# PISO3.net
KiCad netlist of a schematic drawn in EAGLE
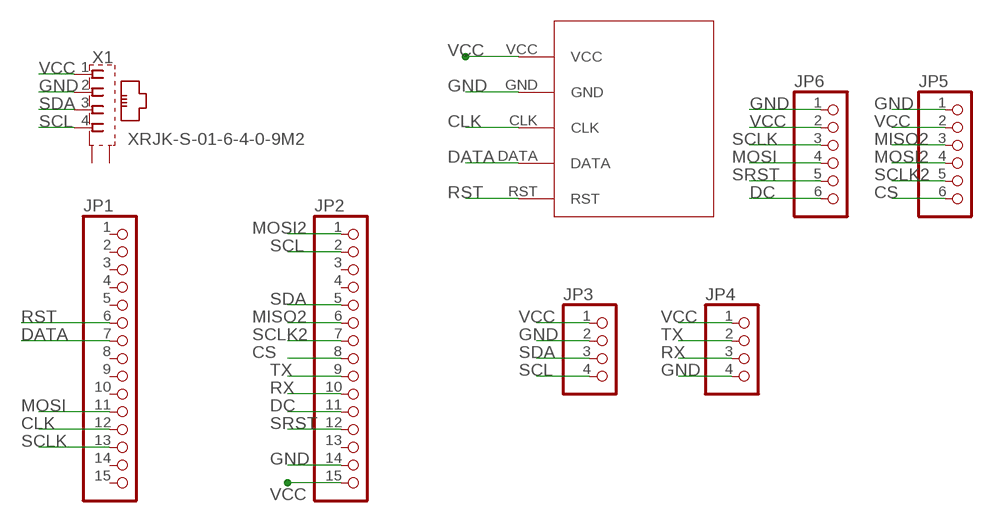
[diagram p0: schematic, sheet 1]

(export (version "E")
  (design (tool "Eeschema 10.0.6"))
  (components
    (comp (ref "JP1")
      (value "PINHD-1X15")
      (footprint "eagle-import:1X15")
      (libsource (lib "eagle-import") (part "PINHD-1X15"))
    )
    (comp (ref "JP2")
      (value "PINHD-1X15")
      (footprint "eagle-import:1X15")
      (libsource (lib "eagle-import") (part "PINHD-1X15"))
    )
    (comp (ref "JP3")
      (value "PINHD-1X4")
      (footprint "eagle-import:1X04")
      (libsource (lib "eagle-import") (part "PINHD-1X4"))
    )
    (comp (ref "JP4")
      (value "PINHD-1X4")
      (footprint "eagle-import:1X04")
      (libsource (lib "eagle-import") (part "PINHD-1X4"))
    )
    (comp (ref "JP5")
      (value "PINHD-1X6")
      (footprint "eagle-import:1X06")
      (libsource (lib "eagle-import") (part "PINHD-1X6"))
    )
    (comp (ref "JP6")
      (value "PINHD-1X6")
      (footprint "eagle-import:1X06")
      (libsource (lib "eagle-import") (part "PINHD-1X6"))
    )
    (comp (ref "U$1")
      (value "DS1302_MODULE")
      (footprint "eagle-import:DS1307_MODULE")
      (libsource (lib "eagle-import") (part "DS1302_MODULE"))
    )
    (comp (ref "X1")
      (value "XRJK-S-01-6-4-0-9M2")
      (footprint "eagle-import:XRJK-S-01-6-4-0-9M2")
      (libsource (lib "eagle-import") (part "XRJK4-0-9M2-S-01-6-"))
    )
  )
  (nets
    (net (code "1") (name "/CLK") (class "Default")
      (node (ref "JP1") (pin "12") (pinfunction "12_12") (pintype "passive"))
      (node (ref "U$1") (pin "CLK") (pinfunction "CLK_CLK") (pintype "bidirectional"))
    )
    (net (code "2") (name "/CS") (class "Default")
      (node (ref "JP2") (pin "8") (pinfunction "8_8") (pintype "passive"))
      (node (ref "JP5") (pin "6") (pinfunction "6_6") (pintype "passive"))
    )
    (net (code "3") (name "/DATA") (class "Default")
      (node (ref "JP1") (pin "7") (pinfunction "7_7") (pintype "passive"))
      (node (ref "U$1") (pin "DATA") (pinfunction "DATA_DATA") (pintype "bidirectional"))
    )
    (net (code "4") (name "/DC") (class "Default")
      (node (ref "JP2") (pin "11") (pinfunction "11_11") (pintype "passive"))
      (node (ref "JP6") (pin "6") (pinfunction "6_6") (pintype "passive"))
    )
    (net (code "5") (name "/GND") (class "Default")
      (node (ref "JP2") (pin "14") (pinfunction "14_14") (pintype "passive"))
      (node (ref "JP3") (pin "2") (pinfunction "2_2") (pintype "passive"))
      (node (ref "JP4") (pin "4") (pinfunction "4_4") (pintype "passive"))
      (node (ref "JP5") (pin "1") (pinfunction "1_1") (pintype "passive"))
      (node (ref "JP6") (pin "1") (pinfunction "1_1") (pintype "passive"))
      (node (ref "U$1") (pin "GND") (pinfunction "GND_GND") (pintype "bidirectional"))
      (node (ref "X1") (pin "2") (pinfunction "2_2") (pintype "passive"))
    )
    (net (code "6") (name "/MISO2") (class "Default")
      (node (ref "JP2") (pin "6") (pinfunction "6_6") (pintype "passive"))
      (node (ref "JP5") (pin "3") (pinfunction "3_3") (pintype "passive"))
    )
    (net (code "7") (name "/MOSI") (class "Default")
      (node (ref "JP1") (pin "11") (pinfunction "11_11") (pintype "passive"))
      (node (ref "JP6") (pin "4") (pinfunction "4_4") (pintype "passive"))
    )
    (net (code "8") (name "/MOSI2") (class "Default")
      (node (ref "JP2") (pin "1") (pinfunction "1_1") (pintype "passive"))
      (node (ref "JP5") (pin "4") (pinfunction "4_4") (pintype "passive"))
    )
    (net (code "9") (name "/RST") (class "Default")
      (node (ref "JP1") (pin "6") (pinfunction "6_6") (pintype "passive"))
      (node (ref "U$1") (pin "RST") (pinfunction "RST_RST") (pintype "bidirectional"))
    )
    (net (code "10") (name "/RX") (class "Default")
      (node (ref "JP2") (pin "10") (pinfunction "10_10") (pintype "passive"))
      (node (ref "JP4") (pin "3") (pinfunction "3_3") (pintype "passive"))
    )
    (net (code "11") (name "/SCL") (class "Default")
      (node (ref "JP2") (pin "2") (pinfunction "2_2") (pintype "passive"))
      (node (ref "JP3") (pin "4") (pinfunction "4_4") (pintype "passive"))
      (node (ref "X1") (pin "4") (pinfunction "4_4") (pintype "passive"))
    )
    (net (code "12") (name "/SCLK") (class "Default")
      (node (ref "JP1") (pin "13") (pinfunction "13_13") (pintype "passive"))
      (node (ref "JP6") (pin "3") (pinfunction "3_3") (pintype "passive"))
    )
    (net (code "13") (name "/SCLK2") (class "Default")
      (node (ref "JP2") (pin "7") (pinfunction "7_7") (pintype "passive"))
      (node (ref "JP5") (pin "5") (pinfunction "5_5") (pintype "passive"))
    )
    (net (code "14") (name "/SDA") (class "Default")
      (node (ref "JP2") (pin "5") (pinfunction "5_5") (pintype "passive"))
      (node (ref "JP3") (pin "3") (pinfunction "3_3") (pintype "passive"))
      (node (ref "X1") (pin "3") (pinfunction "3_3") (pintype "passive"))
    )
    (net (code "15") (name "/SRST") (class "Default")
      (node (ref "JP2") (pin "12") (pinfunction "12_12") (pintype "passive"))
      (node (ref "JP6") (pin "5") (pinfunction "5_5") (pintype "passive"))
    )
    (net (code "16") (name "/TX") (class "Default")
      (node (ref "JP2") (pin "9") (pinfunction "9_9") (pintype "passive"))
      (node (ref "JP4") (pin "2") (pinfunction "2_2") (pintype "passive"))
    )
    (net (code "17") (name "/VCC") (class "Default")
      (node (ref "JP2") (pin "15") (pinfunction "15_15") (pintype "passive"))
      (node (ref "JP3") (pin "1") (pinfunction "1_1") (pintype "passive"))
      (node (ref "JP4") (pin "1") (pinfunction "1_1") (pintype "passive"))
      (node (ref "JP5") (pin "2") (pinfunction "2_2") (pintype "passive"))
      (node (ref "JP6") (pin "2") (pinfunction "2_2") (pintype "passive"))
      (node (ref "U$1") (pin "VCC") (pinfunction "VCC_VCC") (pintype "bidirectional"))
      (node (ref "X1") (pin "1") (pinfunction "1_1") (pintype "passive"))
    )
    (net (code "18") (name "unconnected-(JP1-Pad1)") (class "Default")
      (node (ref "JP1") (pin "1") (pinfunction "1_1") (pintype "passive"))
    )
    (net (code "19") (name "unconnected-(JP1-Pad2)") (class "Default")
      (node (ref "JP1") (pin "2") (pinfunction "2_2") (pintype "passive"))
    )
    (net (code "20") (name "unconnected-(JP1-Pad3)") (class "Default")
      (node (ref "JP1") (pin "3") (pinfunction "3_3") (pintype "passive"))
    )
    (net (code "21") (name "unconnected-(JP1-Pad4)") (class "Default")
      (node (ref "JP1") (pin "4") (pinfunction "4_4") (pintype "passive"))
    )
    (net (code "22") (name "unconnected-(JP1-Pad5)") (class "Default")
      (node (ref "JP1") (pin "5") (pinfunction "5_5") (pintype "passive"))
    )
    (net (code "23") (name "unconnected-(JP1-Pad8)") (class "Default")
      (node (ref "JP1") (pin "8") (pinfunction "8_8") (pintype "passive"))
    )
    (net (code "24") (name "unconnected-(JP1-Pad9)") (class "Default")
      (node (ref "JP1") (pin "9") (pinfunction "9_9") (pintype "passive"))
    )
    (net (code "25") (name "unconnected-(JP1-Pad10)") (class "Default")
      (node (ref "JP1") (pin "10") (pinfunction "10_10") (pintype "passive"))
    )
    (net (code "26") (name "unconnected-(JP1-Pad14)") (class "Default")
      (node (ref "JP1") (pin "14") (pinfunction "14_14") (pintype "passive"))
    )
    (net (code "27") (name "unconnected-(JP1-Pad15)") (class "Default")
      (node (ref "JP1") (pin "15") (pinfunction "15_15") (pintype "passive"))
    )
    (net (code "28") (name "unconnected-(JP2-Pad3)") (class "Default")
      (node (ref "JP2") (pin "3") (pinfunction "3_3") (pintype "passive"))
    )
    (net (code "29") (name "unconnected-(JP2-Pad4)") (class "Default")
      (node (ref "JP2") (pin "4") (pinfunction "4_4") (pintype "passive"))
    )
    (net (code "30") (name "unconnected-(JP2-Pad13)") (class "Default")
      (node (ref "JP2") (pin "13") (pinfunction "13_13") (pintype "passive"))
    )
    (net (code "31") (name "unconnected-(X1-S-PadS1)") (class "Default")
      (node (ref "X1") (pin "S1") (pinfunction "S_S1") (pintype "passive"))
    )
    (net (code "32") (name "unconnected-(X1-S-PadS2)") (class "Default")
      (node (ref "X1") (pin "S2") (pinfunction "S_S2") (pintype "passive"))
    )
  )
)
